# Power_Entry.net
KiCad netlist of a schematic drawn in EAGLE
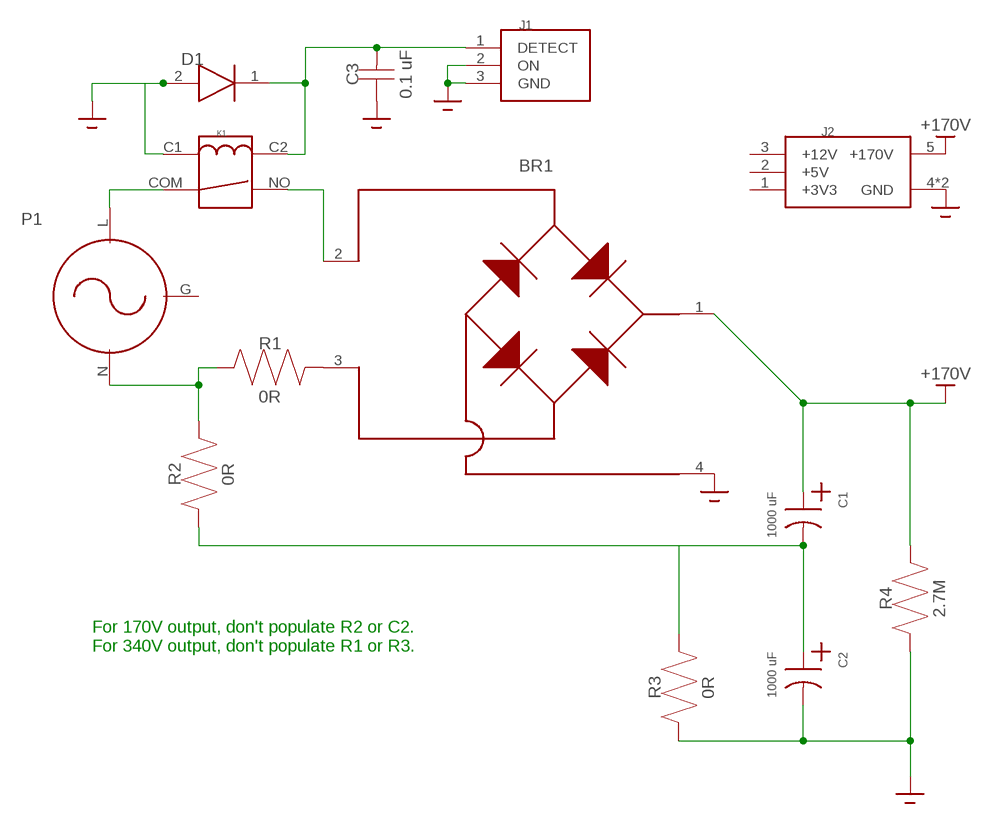
[diagram p0: schematic, sheet 1]

(export (version "E")
  (design (tool "Eeschema 10.0.6"))
  (components
    (comp (ref "BR1")
      (value "GBJ1004-BP")
      (footprint "eagle-import:GBJ1004-BP")
      (libsource (lib "eagle-import") (part "GBJ1004-BP"))
    )
    (comp (ref "C1")
      (value "1000 uF")
      (footprint "eagle-import:ESMQ351VSN102MA50S")
      (libsource (lib "eagle-import") (part "ESMQ351VSN102MA50S"))
    )
    (comp (ref "C2")
      (value "1000 uF")
      (footprint "eagle-import:ESMQ351VSN102MA50S")
      (libsource (lib "eagle-import") (part "ESMQ351VSN102MA50S"))
    )
    (comp (ref "C3")
      (value "0.1 uF")
      (footprint "eagle-import:0805")
      (libsource (lib "eagle-import") (part "CAPACITOR0805"))
    )
    (comp (ref "D1")
      (value "BAT54HT1GBAT54HT1G")
      (footprint "eagle-import:SOD2512X110N")
      (libsource (lib "eagle-import") (part "BAT54HT1GBAT54HT1G"))
    )
    (comp (ref "J1")
      (value "1-770967-0")
      (footprint "eagle-import:1-770967-0")
      (libsource (lib "eagle-import") (part "1-770967-0"))
    )
    (comp (ref "J2")
      (value "1-770969-0")
      (footprint "eagle-import:1-770969-0")
      (libsource (lib "eagle-import") (part "1-770969-0"))
    )
    (comp (ref "K1")
      (value "ALQ3F12")
      (footprint "eagle-import:ALQ3F12")
      (libsource (lib "eagle-import") (part "ALQ3F12"))
    )
    (comp (ref "P1")
      (value "703W-00/04")
      (footprint "eagle-import:703W-00_04")
      (libsource (lib "eagle-import") (part "703W-00/04"))
    )
    (comp (ref "R1")
      (value "0R")
      (footprint "eagle-import:0805")
      (libsource (lib "eagle-import") (part "RESISTOR0805"))
    )
    (comp (ref "R2")
      (value "0R")
      (footprint "eagle-import:0805")
      (libsource (lib "eagle-import") (part "RESISTOR0805"))
    )
    (comp (ref "R3")
      (value "0R")
      (footprint "eagle-import:0805")
      (libsource (lib "eagle-import") (part "RESISTOR0805"))
    )
    (comp (ref "R4")
      (value "2.7M")
      (footprint "eagle-import:0805")
      (libsource (lib "eagle-import") (part "RESISTOR0805"))
    )
  )
  (nets
    (net (code "1") (name "+170V") (class "Default")
      (node (ref "BR1") (pin "1") (pinfunction "POSITIVE_DC_1") (pintype "bidirectional"))
      (node (ref "C1") (pin "+") (pinfunction "+_+") (pintype "passive"))
      (node (ref "J2") (pin "5") (pinfunction "+170V_5") (pintype "power_in"))
      (node (ref "R4") (pin "P$2") (pinfunction "P$2_P$2") (pintype "passive"))
    )
    (net (code "2") (name "/+3V3") (class "Default")
      (node (ref "J2") (pin "1") (pinfunction "+3V3_1") (pintype "power_in"))
    )
    (net (code "3") (name "/+5V") (class "Default")
      (node (ref "J2") (pin "2") (pinfunction "+5V_2") (pintype "power_in"))
    )
    (net (code "4") (name "/+12V") (class "Default")
      (node (ref "J2") (pin "3") (pinfunction "+12V_3") (pintype "power_in"))
    )
    (net (code "5") (name "GND") (class "Default")
      (node (ref "BR1") (pin "4") (pinfunction "NEGATIVE_DC_4") (pintype "bidirectional"))
      (node (ref "C2") (pin "-") (pinfunction "-_-") (pintype "passive"))
      (node (ref "C3") (pin "P$1") (pinfunction "P$1_P$1") (pintype "passive"))
      (node (ref "D1") (pin "2") (pinfunction "ANODE(2)_2") (pintype "bidirectional"))
      (node (ref "J1") (pin "2") (pinfunction "ON_2") (pintype "output"))
      (node (ref "J1") (pin "3") (pinfunction "GND_3") (pintype "passive"))
      (node (ref "J2") (pin "4") (pinfunction "GND_4") (pintype "passive"))
      (node (ref "J2") (pin "6") (pinfunction "GND_6") (pintype "passive"))
      (node (ref "K1") (pin "C1") (pinfunction "C1_C1") (pintype "bidirectional"))
      (node (ref "R3") (pin "P$1") (pinfunction "P$1_P$1") (pintype "passive"))
      (node (ref "R4") (pin "P$1") (pinfunction "P$1_P$1") (pintype "passive"))
    )
    (net (code "6") (name "Net-(BR1-AC_IN1)") (class "Default")
      (node (ref "BR1") (pin "2") (pinfunction "AC_IN1_2") (pintype "bidirectional"))
      (node (ref "K1") (pin "NO") (pinfunction "S2_NO") (pintype "bidirectional"))
    )
    (net (code "7") (name "Net-(BR1-AC_IN2)") (class "Default")
      (node (ref "BR1") (pin "3") (pinfunction "AC_IN2_3") (pintype "bidirectional"))
      (node (ref "R1") (pin "P$2") (pinfunction "P$2_P$2") (pintype "passive"))
    )
    (net (code "8") (name "Net-(C1-Pad-)") (class "Default")
      (node (ref "C1") (pin "-") (pinfunction "-_-") (pintype "passive"))
      (node (ref "C2") (pin "+") (pinfunction "+_+") (pintype "passive"))
      (node (ref "R2") (pin "P$1") (pinfunction "P$1_P$1") (pintype "passive"))
      (node (ref "R3") (pin "P$2") (pinfunction "P$2_P$2") (pintype "passive"))
    )
    (net (code "9") (name "Net-(D1-CATHODE(1))") (class "Default")
      (node (ref "C3") (pin "P$2") (pinfunction "P$2_P$2") (pintype "passive"))
      (node (ref "D1") (pin "1") (pinfunction "CATHODE(1)_1") (pintype "bidirectional"))
      (node (ref "J1") (pin "1") (pinfunction "DETECT_1") (pintype "power_in"))
      (node (ref "K1") (pin "C2") (pinfunction "C2_C2") (pintype "bidirectional"))
    )
    (net (code "10") (name "Net-(K1-S1)") (class "Default")
      (node (ref "K1") (pin "COM") (pinfunction "S1_COM") (pintype "bidirectional"))
      (node (ref "P1") (pin "L") (pinfunction "LIVE_L") (pintype "bidirectional"))
    )
    (net (code "11") (name "Net-(P1-NEUTRAL)") (class "Default")
      (node (ref "P1") (pin "N") (pinfunction "NEUTRAL_N") (pintype "bidirectional"))
      (node (ref "R1") (pin "P$1") (pinfunction "P$1_P$1") (pintype "passive"))
      (node (ref "R2") (pin "P$2") (pinfunction "P$2_P$2") (pintype "passive"))
    )
    (net (code "12") (name "unconnected-(P1-EARTH-PadG)") (class "Default")
      (node (ref "P1") (pin "G") (pinfunction "EARTH_G") (pintype "bidirectional"))
    )
  )
)
